# SCH_HackerCard_2024-08-29.net
KiCad netlist of a schematic drawn in EasyEDA
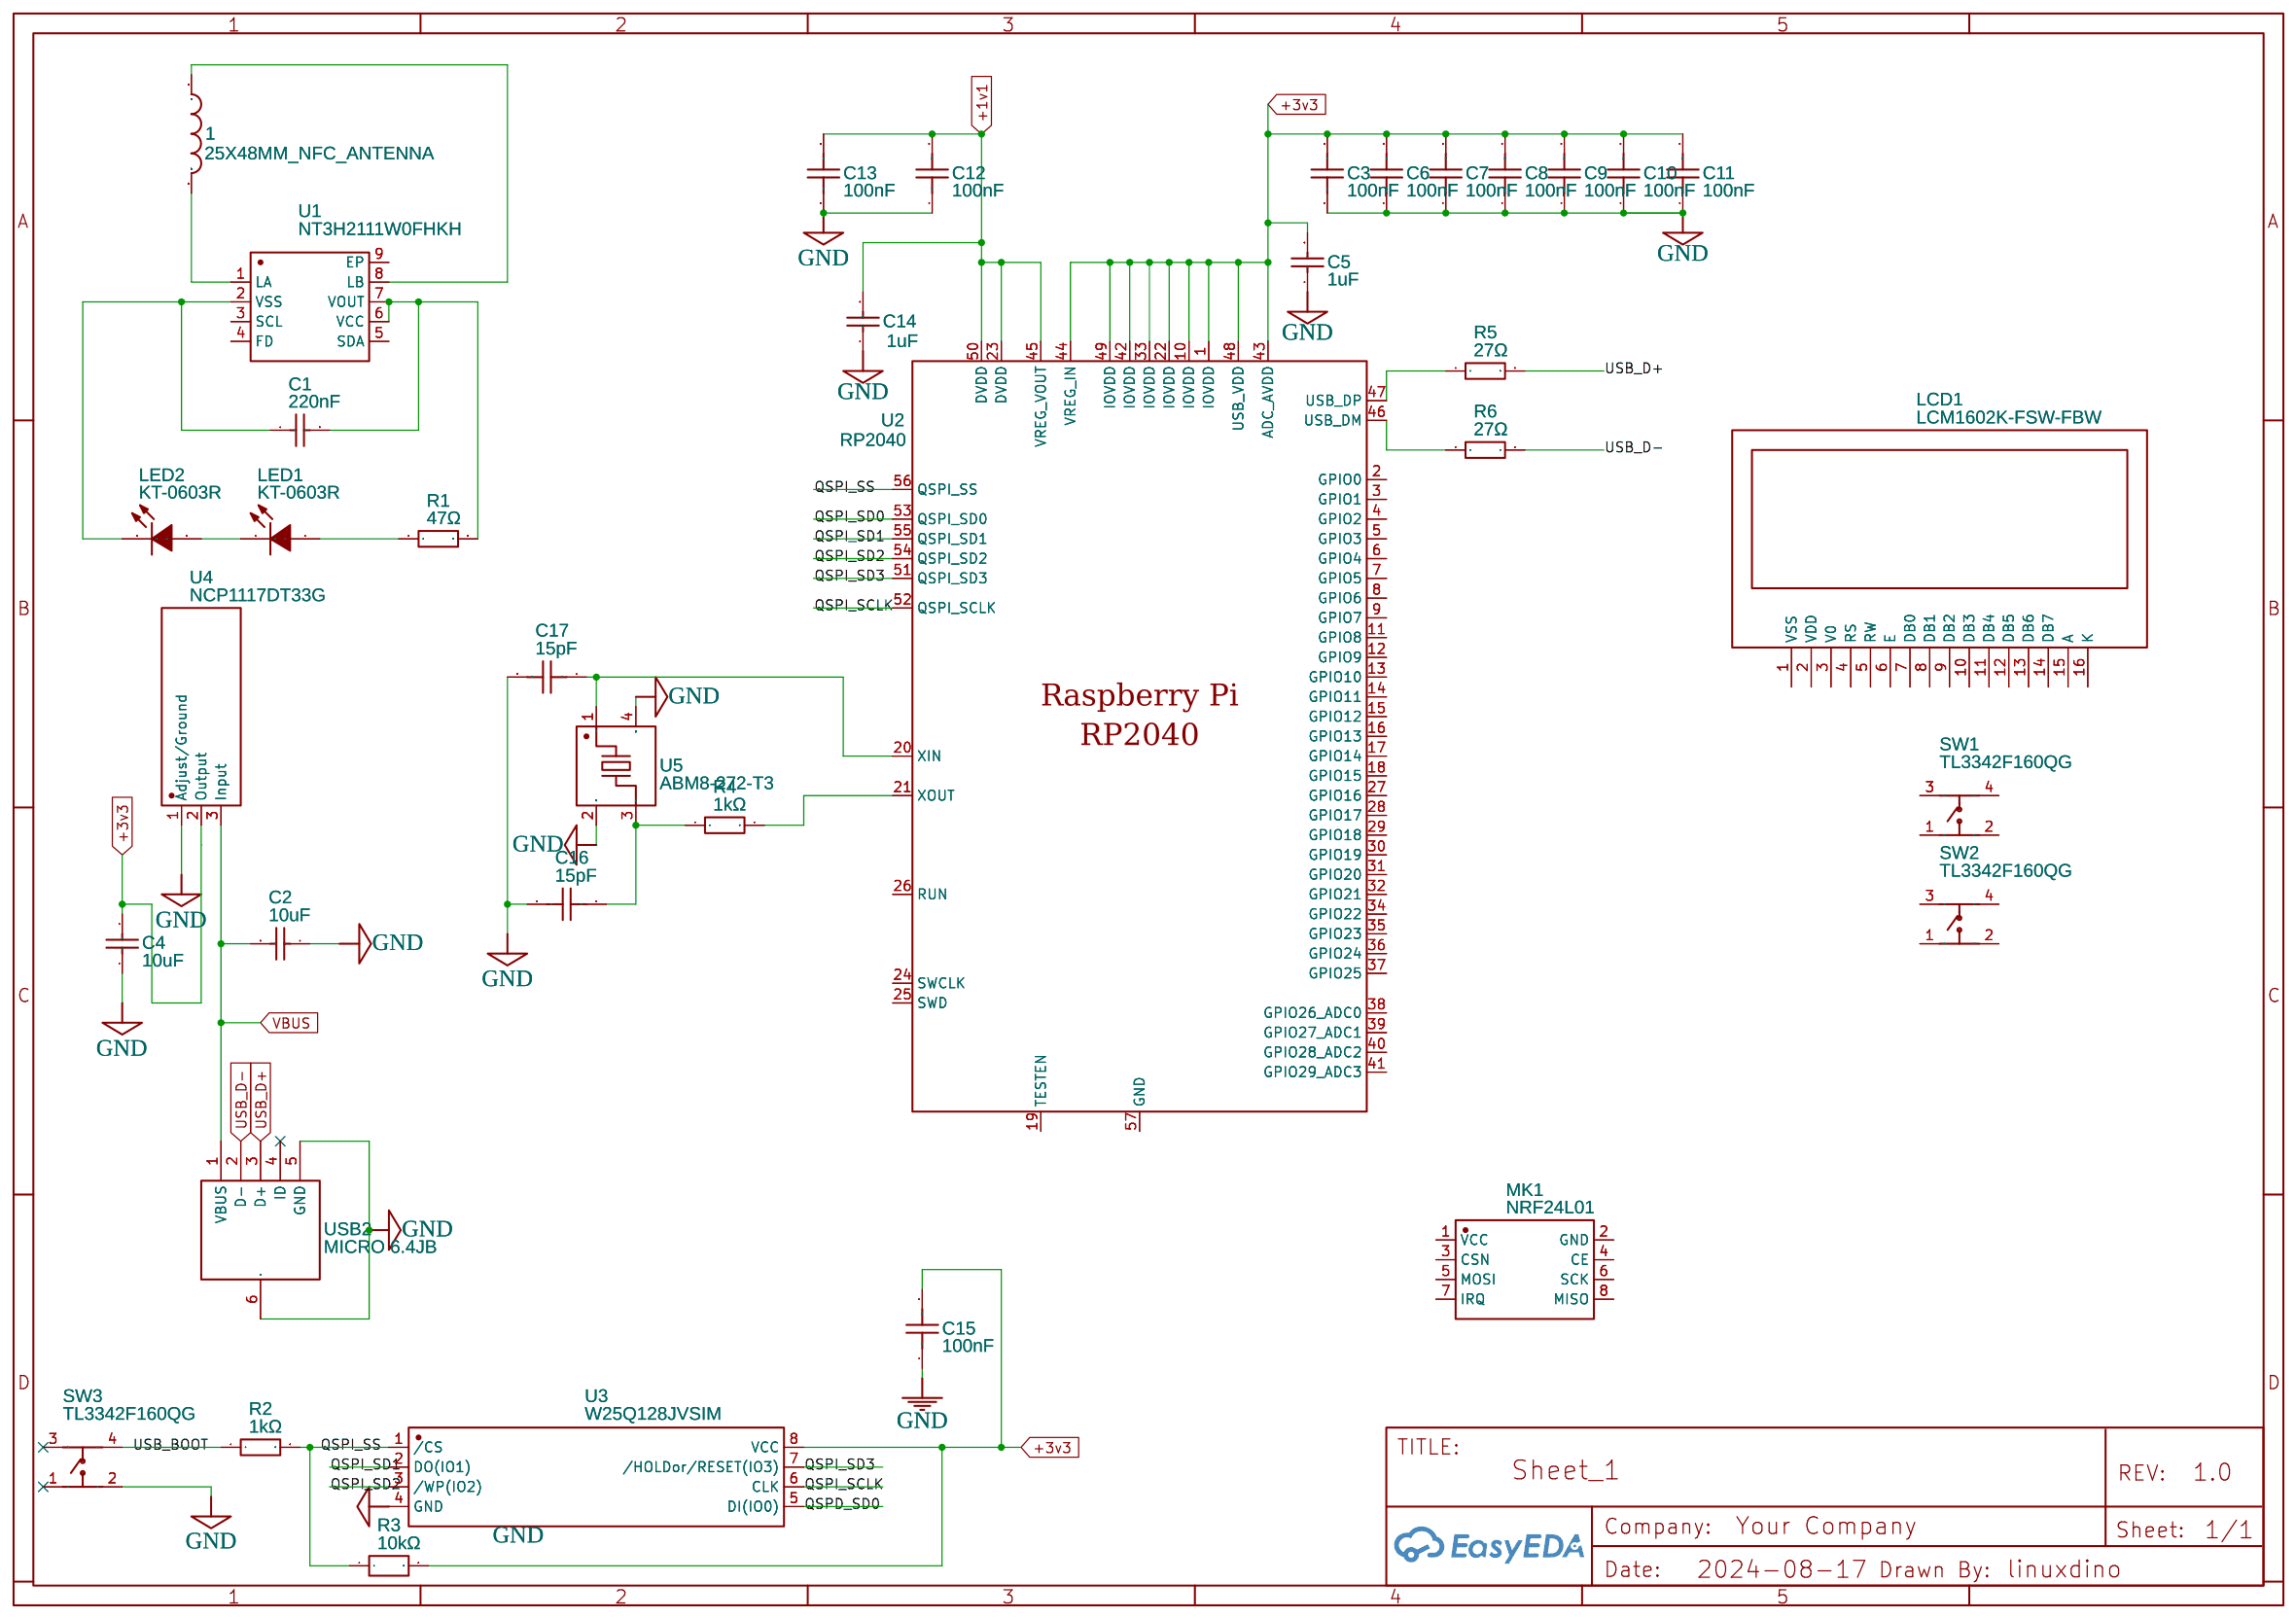
[diagram p0: schematic sheet]

(export (version "E")
  (design (tool "Eeschema 10.0.6"))
  (components
    (comp (ref "1") (value "25X48MM_NFC_ANTENNA") (libsource (lib "") (part "25X48MM_NFC_ANTENNA")))
    (comp (ref "C1")
      (value "220nF")
      (fields
        (field (name "Manufacturer Part") "CL10B224KA8NNNC")
        (field (name "Manufacturer") "SAMSUNG(三星)")
      )
      (libsource (lib "") (part "CL10B224KA8NNNC"))
    )
    (comp (ref "C2")
      (value "10uF")
      (fields
        (field (name "Manufacturer Part") "CL31A106KOHNNNE")
        (field (name "Manufacturer") "SAMSUNG(三星)")
      )
      (libsource (lib "") (part "CL31A106KOHNNNE_1"))
    )
    (comp (ref "C3")
      (value "100nF")
      (fields
        (field (name "Manufacturer Part") "CL10B104KB8NNNC")
        (field (name "Manufacturer") "SAMSUNG(三星)")
      )
      (libsource (lib "") (part "CL10B104KB8NNNC"))
    )
    (comp (ref "C4")
      (value "10uF")
      (fields
        (field (name "Manufacturer Part") "CL31A106KOHNNNE")
        (field (name "Manufacturer") "SAMSUNG(三星)")
      )
      (libsource (lib "") (part "CL31A106KOHNNNE"))
    )
    (comp (ref "C5")
      (value "1uF")
      (fields
        (field (name "Manufacturer Part") "CL10A105KO8NNNC")
        (field (name "Manufacturer") "SAMSUNG(三星)")
      )
      (libsource (lib "") (part "CL10A105KO8NNNC"))
    )
    (comp (ref "C6")
      (value "100nF")
      (fields
        (field (name "Manufacturer Part") "CL10B104KB8NNNC")
        (field (name "Manufacturer") "SAMSUNG(三星)")
      )
      (libsource (lib "") (part "CL10B104KB8NNNC"))
    )
    (comp (ref "C7")
      (value "100nF")
      (fields
        (field (name "Manufacturer Part") "CL10B104KB8NNNC")
        (field (name "Manufacturer") "SAMSUNG(三星)")
      )
      (libsource (lib "") (part "CL10B104KB8NNNC"))
    )
    (comp (ref "C8")
      (value "100nF")
      (fields
        (field (name "Manufacturer Part") "CL10B104KB8NNNC")
        (field (name "Manufacturer") "SAMSUNG(三星)")
      )
      (libsource (lib "") (part "CL10B104KB8NNNC"))
    )
    (comp (ref "C9")
      (value "100nF")
      (fields
        (field (name "Manufacturer Part") "CL10B104KB8NNNC")
        (field (name "Manufacturer") "SAMSUNG(三星)")
      )
      (libsource (lib "") (part "CL10B104KB8NNNC"))
    )
    (comp (ref "C10")
      (value "100nF")
      (fields
        (field (name "Manufacturer Part") "CL10B104KB8NNNC")
        (field (name "Manufacturer") "SAMSUNG(三星)")
      )
      (libsource (lib "") (part "CL10B104KB8NNNC"))
    )
    (comp (ref "C11")
      (value "100nF")
      (fields
        (field (name "Manufacturer Part") "CL10B104KB8NNNC")
        (field (name "Manufacturer") "SAMSUNG(三星)")
      )
      (libsource (lib "") (part "CL10B104KB8NNNC"))
    )
    (comp (ref "C12")
      (value "100nF")
      (fields
        (field (name "Manufacturer Part") "CL10B104KB8NNNC")
        (field (name "Manufacturer") "SAMSUNG(三星)")
      )
      (libsource (lib "") (part "CL10B104KB8NNNC"))
    )
    (comp (ref "C13")
      (value "100nF")
      (fields
        (field (name "Manufacturer Part") "CL10B104KB8NNNC")
        (field (name "Manufacturer") "SAMSUNG(三星)")
      )
      (libsource (lib "") (part "CL10B104KB8NNNC"))
    )
    (comp (ref "C14")
      (value "1uF")
      (fields
        (field (name "Manufacturer Part") "CL10A105KO8NNNC")
        (field (name "Manufacturer") "SAMSUNG(三星)")
      )
      (libsource (lib "") (part "CL10A105KO8NNNC"))
    )
    (comp (ref "C15")
      (value "100nF")
      (fields
        (field (name "Manufacturer Part") "CL10B104KB8NNNC")
        (field (name "Manufacturer") "SAMSUNG(三星)")
      )
      (libsource (lib "") (part "CL10B104KB8NNNC"))
    )
    (comp (ref "C16")
      (value "15pF")
      (fields (field (name "Manufacturer Part") "RF15N150J500CT") (field (name "Manufacturer") "Walsin(华新科)"))
      (libsource (lib "") (part "RF15N150J500CT"))
    )
    (comp (ref "C17")
      (value "15pF")
      (fields (field (name "Manufacturer Part") "RF15N150J500CT") (field (name "Manufacturer") "Walsin(华新科)"))
      (libsource (lib "") (part "RF15N150J500CT"))
    )
    (comp (ref "LCD1")
      (value "LCM1602K-FSW-FBW")
      (fields (field (name "Manufacturer") "LONTECH(厦门龙特)"))
      (libsource (lib "") (part "LCM1602K-FSW-FBW"))
    )
    (comp (ref "LED1")
      (value "KT-0603R")
      (fields (field (name "Manufacturer") "KENTO"))
      (libsource (lib "") (part "KT-0603R"))
    )
    (comp (ref "LED2")
      (value "KT-0603R")
      (fields (field (name "Manufacturer") "KENTO"))
      (libsource (lib "") (part "KT-0603R"))
    )
    (comp (ref "MK1")
      (value "NRF24L01")
      (fields (field (name "Manufacturer Part") "NF-04") (field (name "Manufacturer") "Ai-Thinker(安信可)"))
      (libsource (lib "") (part "NRF24L01"))
    )
    (comp (ref "R1")
      (value "47Ω")
      (fields
        (field (name "Manufacturer Part") "0603WAF470JT5E")
        (field (name "Manufacturer") "UNI-ROYAL(厚声)")
      )
      (libsource (lib "") (part "0603WAF470JT5E"))
    )
    (comp (ref "R2")
      (value "1kΩ")
      (fields
        (field (name "Manufacturer Part") "0603WAF1001T5E")
        (field (name "Manufacturer") "UNI-ROYAL(厚声)")
      )
      (libsource (lib "") (part "0603WAF1001T5E"))
    )
    (comp (ref "R3")
      (value "10kΩ")
      (fields (field (name "Manufacturer Part") "CR-03JL7---10K") (field (name "Manufacturer") "Viking(光颉)"))
      (libsource (lib "") (part "CR-03JL7---10K"))
    )
    (comp (ref "R4")
      (value "1kΩ")
      (fields
        (field (name "Manufacturer Part") "0603WAF1001T5E")
        (field (name "Manufacturer") "UNI-ROYAL(厚声)")
      )
      (libsource (lib "") (part "0603WAF1001T5E"))
    )
    (comp (ref "R5")
      (value "27Ω")
      (fields (field (name "Manufacturer Part") "RN732ATTD27R0B25") (field (name "Manufacturer") "KOA"))
      (libsource (lib "") (part "RN732ATTD27R0B25"))
    )
    (comp (ref "R6")
      (value "27Ω")
      (fields (field (name "Manufacturer Part") "RN732ATTD27R0B25") (field (name "Manufacturer") "KOA"))
      (libsource (lib "") (part "RN732ATTD27R0B25"))
    )
    (comp (ref "SW1")
      (value "TL3342F160QG")
      (fields (field (name "Manufacturer") "E-Switch"))
      (libsource (lib "") (part "TL3342F160QG"))
    )
    (comp (ref "SW2")
      (value "TL3342F160QG")
      (fields (field (name "Manufacturer") "E-Switch"))
      (libsource (lib "") (part "TL3342F160QG"))
    )
    (comp (ref "SW3")
      (value "TL3342F160QG")
      (fields (field (name "Manufacturer") "E-Switch"))
      (libsource (lib "") (part "TL3342F160QG"))
    )
    (comp (ref "U1")
      (value "NT3H2111W0FHKH")
      (fields (field (name "Manufacturer") "NXP(恩智浦)"))
      (libsource (lib "") (part "NT3H2111W0FHKH"))
    )
    (comp (ref "U2")
      (value "RP2040")
      (fields (field (name "Manufacturer") "Raspberry Pi(树莓派)"))
      (libsource (lib "") (part "RP2040"))
    )
    (comp (ref "U3")
      (value "W25Q128JVSIM")
      (fields (field (name "Manufacturer") "WINBOND(华邦)"))
      (libsource (lib "") (part "W25Q128JVSIM"))
    )
    (comp (ref "U4")
      (value "NCP1117DT33G")
      (fields (field (name "Manufacturer") "onsemi(安森美)"))
      (libsource (lib "") (part "NCP1117DT33G"))
    )
    (comp (ref "U5") (value "ABM8-272-T3") (libsource (lib "") (part "ABM8-272-T3")))
    (comp (ref "USB2")
      (value "MICRO 6.4JB")
      (fields (field (name "Manufacturer") "SHOU HAN(首韩)"))
      (libsource (lib "") (part "MICRO 6.4JB"))
    )
  )
  (nets
    (net (code "1") (name "+1v1") (class "Default")
      (node (ref "C12") (pin "2") (pinfunction "2_2") (pintype "unspecified"))
      (node (ref "C13") (pin "2") (pinfunction "2_2") (pintype "unspecified"))
      (node (ref "C14") (pin "2") (pinfunction "2_2") (pintype "input"))
      (node (ref "U2") (pin "23") (pinfunction "DVDD_23") (pintype "bidirectional"))
      (node (ref "U2") (pin "45") (pinfunction "VREG_VOUT_45") (pintype "bidirectional"))
      (node (ref "U2") (pin "50") (pinfunction "DVDD_50") (pintype "bidirectional"))
    )
    (net (code "2") (name "+3v3") (class "Default")
      (node (ref "C10") (pin "2") (pinfunction "2_2") (pintype "unspecified"))
      (node (ref "C11") (pin "2") (pinfunction "2_2") (pintype "unspecified"))
      (node (ref "C15") (pin "2") (pinfunction "2_2") (pintype "unspecified"))
      (node (ref "C3") (pin "2") (pinfunction "2_2") (pintype "unspecified"))
      (node (ref "C4") (pin "2") (pinfunction "2_2") (pintype "input"))
      (node (ref "C5") (pin "2") (pinfunction "2_2") (pintype "input"))
      (node (ref "C6") (pin "2") (pinfunction "2_2") (pintype "unspecified"))
      (node (ref "C7") (pin "2") (pinfunction "2_2") (pintype "unspecified"))
      (node (ref "C8") (pin "2") (pinfunction "2_2") (pintype "unspecified"))
      (node (ref "C9") (pin "2") (pinfunction "2_2") (pintype "unspecified"))
      (node (ref "R3") (pin "2") (pinfunction "2_2") (pintype "unspecified"))
      (node (ref "U2") (pin "1") (pinfunction "IOVDD_1") (pintype "bidirectional"))
      (node (ref "U2") (pin "10") (pinfunction "IOVDD_10") (pintype "bidirectional"))
      (node (ref "U2") (pin "22") (pinfunction "IOVDD_22") (pintype "bidirectional"))
      (node (ref "U2") (pin "33") (pinfunction "IOVDD_33") (pintype "bidirectional"))
      (node (ref "U2") (pin "42") (pinfunction "IOVDD_42") (pintype "bidirectional"))
      (node (ref "U2") (pin "43") (pinfunction "ADC_AVDD_43") (pintype "bidirectional"))
      (node (ref "U2") (pin "44") (pinfunction "VREG_IN_44") (pintype "bidirectional"))
      (node (ref "U2") (pin "48") (pinfunction "USB_VDD_48") (pintype "bidirectional"))
      (node (ref "U2") (pin "49") (pinfunction "IOVDD_49") (pintype "bidirectional"))
      (node (ref "U3") (pin "8") (pinfunction "VCC_8") (pintype "unspecified"))
      (node (ref "U4") (pin "2") (pinfunction "Output_2") (pintype "unspecified"))
    )
    (net (code "3") (name "/QSPD_SD0") (class "Default")
      (node (ref "U3") (pin "5") (pinfunction "DI(IO0)_5") (pintype "unspecified"))
    )
    (net (code "4") (name "/QSPI_SCLK") (class "Default")
      (node (ref "U2") (pin "52") (pinfunction "QSPI_SCLK_52") (pintype "output"))
      (node (ref "U3") (pin "6") (pinfunction "CLK_6") (pintype "unspecified"))
    )
    (net (code "5") (name "/QSPI_SD0") (class "Default")
      (node (ref "U2") (pin "53") (pinfunction "QSPI_SD0_53") (pintype "bidirectional"))
    )
    (net (code "6") (name "/QSPI_SD1") (class "Default")
      (node (ref "U2") (pin "55") (pinfunction "QSPI_SD1_55") (pintype "bidirectional"))
      (node (ref "U3") (pin "2") (pinfunction "DO(IO1)_2") (pintype "unspecified"))
    )
    (net (code "7") (name "/QSPI_SD2") (class "Default")
      (node (ref "U2") (pin "54") (pinfunction "QSPI_SD2_54") (pintype "bidirectional"))
      (node (ref "U3") (pin "3") (pinfunction "/WP(IO2)_3") (pintype "unspecified"))
    )
    (net (code "8") (name "/QSPI_SD3") (class "Default")
      (node (ref "U2") (pin "51") (pinfunction "QSPI_SD3_51") (pintype "bidirectional"))
      (node (ref "U3") (pin "7") (pinfunction "/HOLDor/RESET(IO3)_7") (pintype "unspecified"))
    )
    (net (code "9") (name "/QSPI_SS") (class "Default")
      (node (ref "R2") (pin "2") (pinfunction "2_2") (pintype "input"))
      (node (ref "R3") (pin "1") (pinfunction "1_1") (pintype "unspecified"))
      (node (ref "U2") (pin "56") (pinfunction "QSPI_SS_56") (pintype "bidirectional"))
      (node (ref "U3") (pin "1") (pinfunction "/CS_1") (pintype "unspecified"))
    )
    (net (code "10") (name "/USB_BOOT") (class "Default")
      (node (ref "R2") (pin "1") (pinfunction "1_1") (pintype "input"))
      (node (ref "SW3") (pin "4") (pinfunction "4_4") (pintype "unspecified"))
    )
    (net (code "11") (name "GND") (class "Default")
      (node (ref "C10") (pin "1") (pinfunction "1_1") (pintype "unspecified"))
      (node (ref "C11") (pin "1") (pinfunction "1_1") (pintype "unspecified"))
      (node (ref "C12") (pin "1") (pinfunction "1_1") (pintype "unspecified"))
      (node (ref "C13") (pin "1") (pinfunction "1_1") (pintype "unspecified"))
      (node (ref "C14") (pin "1") (pinfunction "1_1") (pintype "input"))
      (node (ref "C15") (pin "1") (pinfunction "1_1") (pintype "unspecified"))
      (node (ref "C16") (pin "2") (pinfunction "2_2") (pintype "unspecified"))
      (node (ref "C17") (pin "2") (pinfunction "2_2") (pintype "unspecified"))
      (node (ref "C2") (pin "1") (pinfunction "1_1") (pintype "input"))
      (node (ref "C3") (pin "1") (pinfunction "1_1") (pintype "unspecified"))
      (node (ref "C4") (pin "1") (pinfunction "1_1") (pintype "input"))
      (node (ref "C5") (pin "1") (pinfunction "1_1") (pintype "input"))
      (node (ref "C6") (pin "1") (pinfunction "1_1") (pintype "unspecified"))
      (node (ref "C7") (pin "1") (pinfunction "1_1") (pintype "unspecified"))
      (node (ref "C8") (pin "1") (pinfunction "1_1") (pintype "unspecified"))
      (node (ref "C9") (pin "1") (pinfunction "1_1") (pintype "unspecified"))
      (node (ref "SW3") (pin "2") (pinfunction "2_2") (pintype "unspecified"))
      (node (ref "U3") (pin "4") (pinfunction "GND_4") (pintype "unspecified"))
      (node (ref "U4") (pin "1") (pinfunction "Adjust/Ground_1") (pintype "unspecified"))
      (node (ref "U5") (pin "2") (pinfunction "GND_2") (pintype "input"))
      (node (ref "U5") (pin "4") (pinfunction "GND_4") (pintype "input"))
      (node (ref "USB2") (pin "5") (pinfunction "GND_5") (pintype "input"))
      (node (ref "USB2") (pin "6") (pinfunction "EH_6") (pintype "input"))
    )
    (net (code "12") (name "Net-(C16-Pad1)") (class "Default")
      (node (ref "C16") (pin "1") (pinfunction "1_1") (pintype "unspecified"))
      (node (ref "R4") (pin "1") (pinfunction "1_1") (pintype "input"))
      (node (ref "U5") (pin "3") (pinfunction "3_3") (pintype "input"))
    )
    (net (code "13") (name "Net-(LED1-A)") (class "Default")
      (node (ref "LED1") (pin "2") (pinfunction "A_2") (pintype "unspecified"))
      (node (ref "R1") (pin "1") (pinfunction "1_1") (pintype "input"))
    )
    (net (code "14") (name "Net-(LED1-K)") (class "Default")
      (node (ref "LED1") (pin "1") (pinfunction "K_1") (pintype "unspecified"))
      (node (ref "LED2") (pin "2") (pinfunction "A_2") (pintype "unspecified"))
    )
    (net (code "15") (name "Net-(LED2-K)") (class "Default")
      (node (ref "C1") (pin "1") (pinfunction "1_1") (pintype "input"))
      (node (ref "LED2") (pin "1") (pinfunction "K_1") (pintype "unspecified"))
      (node (ref "U1") (pin "2") (pinfunction "VSS_2") (pintype "unspecified"))
    )
    (net (code "16") (name "Net-(U1-LA)") (class "Default")
      (node (ref "1") (pin "P$2") (pinfunction "P$2_P$2") (pintype "bidirectional"))
      (node (ref "U1") (pin "1") (pinfunction "LA_1") (pintype "unspecified"))
    )
    (net (code "17") (name "Net-(U1-LB)") (class "Default")
      (node (ref "1") (pin "P$1") (pinfunction "P$1_P$1") (pintype "bidirectional"))
      (node (ref "U1") (pin "8") (pinfunction "LB_8") (pintype "unspecified"))
    )
    (net (code "18") (name "Net-(U1-VCC)") (class "Default")
      (node (ref "C1") (pin "2") (pinfunction "2_2") (pintype "input"))
      (node (ref "R1") (pin "2") (pinfunction "2_2") (pintype "input"))
      (node (ref "U1") (pin "6") (pinfunction "VCC_6") (pintype "unspecified"))
      (node (ref "U1") (pin "7") (pinfunction "VOUT_7") (pintype "unspecified"))
    )
    (net (code "19") (name "Net-(U2-USB_DM)") (class "Default")
      (node (ref "R6") (pin "1") (pinfunction "1_1") (pintype "unspecified"))
      (node (ref "U2") (pin "46") (pinfunction "USB_DM_46") (pintype "bidirectional"))
    )
    (net (code "20") (name "Net-(U2-USB_DP)") (class "Default")
      (node (ref "R5") (pin "1") (pinfunction "1_1") (pintype "unspecified"))
      (node (ref "U2") (pin "47") (pinfunction "USB_DP_47") (pintype "bidirectional"))
    )
    (net (code "21") (name "Net-(U2-XIN)") (class "Default")
      (node (ref "C17") (pin "1") (pinfunction "1_1") (pintype "unspecified"))
      (node (ref "U2") (pin "20") (pinfunction "XIN_20") (pintype "input"))
      (node (ref "U5") (pin "1") (pinfunction "1_1") (pintype "input"))
    )
    (net (code "22") (name "Net-(U2-XOUT)") (class "Default")
      (node (ref "R4") (pin "2") (pinfunction "2_2") (pintype "input"))
      (node (ref "U2") (pin "21") (pinfunction "XOUT_21") (pintype "unspecified"))
    )
    (net (code "23") (name "USB_D+") (class "Default")
      (node (ref "R5") (pin "2") (pinfunction "2_2") (pintype "unspecified"))
      (node (ref "USB2") (pin "3") (pinfunction "D+_3") (pintype "input"))
    )
    (net (code "24") (name "USB_D-") (class "Default")
      (node (ref "R6") (pin "2") (pinfunction "2_2") (pintype "unspecified"))
      (node (ref "USB2") (pin "2") (pinfunction "D-_2") (pintype "input"))
    )
    (net (code "25") (name "VBUS") (class "Default")
      (node (ref "C2") (pin "2") (pinfunction "2_2") (pintype "input"))
      (node (ref "U4") (pin "3") (pinfunction "Input_3") (pintype "unspecified"))
      (node (ref "USB2") (pin "1") (pinfunction "VBUS_1") (pintype "input"))
    )
    (net (code "26") (name "unconnected-(LCD1-A-Pad15)") (class "Default")
      (node (ref "LCD1") (pin "15") (pinfunction "A_15") (pintype "unspecified"))
    )
    (net (code "27") (name "unconnected-(LCD1-DB0-Pad7)") (class "Default")
      (node (ref "LCD1") (pin "7") (pinfunction "DB0_7") (pintype "unspecified"))
    )
    (net (code "28") (name "unconnected-(LCD1-DB1-Pad8)") (class "Default")
      (node (ref "LCD1") (pin "8") (pinfunction "DB1_8") (pintype "unspecified"))
    )
    (net (code "29") (name "unconnected-(LCD1-DB2-Pad9)") (class "Default")
      (node (ref "LCD1") (pin "9") (pinfunction "DB2_9") (pintype "unspecified"))
    )
    (net (code "30") (name "unconnected-(LCD1-DB3-Pad10)") (class "Default")
      (node (ref "LCD1") (pin "10") (pinfunction "DB3_10") (pintype "unspecified"))
    )
    (net (code "31") (name "unconnected-(LCD1-DB4-Pad11)") (class "Default")
      (node (ref "LCD1") (pin "11") (pinfunction "DB4_11") (pintype "unspecified"))
    )
    (net (code "32") (name "unconnected-(LCD1-DB5-Pad12)") (class "Default")
      (node (ref "LCD1") (pin "12") (pinfunction "DB5_12") (pintype "unspecified"))
    )
    (net (code "33") (name "unconnected-(LCD1-DB6-Pad13)") (class "Default")
      (node (ref "LCD1") (pin "13") (pinfunction "DB6_13") (pintype "unspecified"))
    )
    (net (code "34") (name "unconnected-(LCD1-DB7-Pad14)") (class "Default")
      (node (ref "LCD1") (pin "14") (pinfunction "DB7_14") (pintype "unspecified"))
    )
    (net (code "35") (name "unconnected-(LCD1-E-Pad6)") (class "Default")
      (node (ref "LCD1") (pin "6") (pinfunction "E_6") (pintype "unspecified"))
    )
    (net (code "36") (name "unconnected-(LCD1-K-Pad16)") (class "Default")
      (node (ref "LCD1") (pin "16") (pinfunction "K_16") (pintype "unspecified"))
    )
    (net (code "37") (name "unconnected-(LCD1-RS-Pad4)") (class "Default")
      (node (ref "LCD1") (pin "4") (pinfunction "RS_4") (pintype "unspecified"))
    )
    (net (code "38") (name "unconnected-(LCD1-RW-Pad5)") (class "Default")
      (node (ref "LCD1") (pin "5") (pinfunction "RW_5") (pintype "unspecified"))
    )
    (net (code "39") (name "unconnected-(LCD1-V0-Pad3)") (class "Default")
      (node (ref "LCD1") (pin "3") (pinfunction "V0_3") (pintype "unspecified"))
    )
    (net (code "40") (name "unconnected-(LCD1-VDD-Pad2)") (class "Default")
      (node (ref "LCD1") (pin "2") (pinfunction "VDD_2") (pintype "unspecified"))
    )
    (net (code "41") (name "unconnected-(LCD1-VSS-Pad1)") (class "Default")
      (node (ref "LCD1") (pin "1") (pinfunction "VSS_1") (pintype "unspecified"))
    )
    (net (code "42") (name "unconnected-(MK1-CE-Pad4)") (class "Default")
      (node (ref "MK1") (pin "4") (pinfunction "CE_4") (pintype "unspecified"))
    )
    (net (code "43") (name "unconnected-(MK1-CSN-Pad3)") (class "Default")
      (node (ref "MK1") (pin "3") (pinfunction "CSN_3") (pintype "unspecified"))
    )
    (net (code "44") (name "unconnected-(MK1-GND-Pad2)") (class "Default")
      (node (ref "MK1") (pin "2") (pinfunction "GND_2") (pintype "unspecified"))
    )
    (net (code "45") (name "unconnected-(MK1-IRQ-Pad7)") (class "Default")
      (node (ref "MK1") (pin "7") (pinfunction "IRQ_7") (pintype "unspecified"))
    )
    (net (code "46") (name "unconnected-(MK1-MISO-Pad8)") (class "Default")
      (node (ref "MK1") (pin "8") (pinfunction "MISO_8") (pintype "unspecified"))
    )
    (net (code "47") (name "unconnected-(MK1-MOSI-Pad5)") (class "Default")
      (node (ref "MK1") (pin "5") (pinfunction "MOSI_5") (pintype "unspecified"))
    )
    (net (code "48") (name "unconnected-(MK1-SCK-Pad6)") (class "Default")
      (node (ref "MK1") (pin "6") (pinfunction "SCK_6") (pintype "unspecified"))
    )
    (net (code "49") (name "unconnected-(MK1-VCC-Pad1)") (class "Default")
      (node (ref "MK1") (pin "1") (pinfunction "VCC_1") (pintype "unspecified"))
    )
    (net (code "50") (name "unconnected-(SW1-Pad1)") (class "Default")
      (node (ref "SW1") (pin "1") (pinfunction "1_1") (pintype "unspecified"))
    )
    (net (code "51") (name "unconnected-(SW1-Pad2)") (class "Default")
      (node (ref "SW1") (pin "2") (pinfunction "2_2") (pintype "unspecified"))
    )
    (net (code "52") (name "unconnected-(SW1-Pad3)") (class "Default")
      (node (ref "SW1") (pin "3") (pinfunction "3_3") (pintype "unspecified"))
    )
    (net (code "53") (name "unconnected-(SW1-Pad4)") (class "Default")
      (node (ref "SW1") (pin "4") (pinfunction "4_4") (pintype "unspecified"))
    )
    (net (code "54") (name "unconnected-(SW2-Pad1)") (class "Default")
      (node (ref "SW2") (pin "1") (pinfunction "1_1") (pintype "unspecified"))
    )
    (net (code "55") (name "unconnected-(SW2-Pad2)") (class "Default")
      (node (ref "SW2") (pin "2") (pinfunction "2_2") (pintype "unspecified"))
    )
    (net (code "56") (name "unconnected-(SW2-Pad3)") (class "Default")
      (node (ref "SW2") (pin "3") (pinfunction "3_3") (pintype "unspecified"))
    )
    (net (code "57") (name "unconnected-(SW2-Pad4)") (class "Default")
      (node (ref "SW2") (pin "4") (pinfunction "4_4") (pintype "unspecified"))
    )
    (net (code "58") (name "unconnected-(SW3-Pad1)") (class "Default")
      (node (ref "SW3") (pin "1") (pinfunction "1_1") (pintype "unspecified+no_connect"))
    )
    (net (code "59") (name "unconnected-(SW3-Pad3)") (class "Default")
      (node (ref "SW3") (pin "3") (pinfunction "3_3") (pintype "unspecified+no_connect"))
    )
    (net (code "60") (name "unconnected-(U1-EP-Pad9)") (class "Default")
      (node (ref "U1") (pin "9") (pinfunction "EP_9") (pintype "unspecified"))
    )
    (net (code "61") (name "unconnected-(U1-FD-Pad4)") (class "Default")
      (node (ref "U1") (pin "4") (pinfunction "FD_4") (pintype "unspecified"))
    )
    (net (code "62") (name "unconnected-(U1-SCL-Pad3)") (class "Default")
      (node (ref "U1") (pin "3") (pinfunction "SCL_3") (pintype "unspecified"))
    )
    (net (code "63") (name "unconnected-(U1-SDA-Pad5)") (class "Default")
      (node (ref "U1") (pin "5") (pinfunction "SDA_5") (pintype "unspecified"))
    )
    (net (code "64") (name "unconnected-(U2-GND-Pad57)") (class "Default")
      (node (ref "U2") (pin "57") (pinfunction "GND_57") (pintype "bidirectional"))
    )
    (net (code "65") (name "unconnected-(U2-GPIO0-Pad2)") (class "Default")
      (node (ref "U2") (pin "2") (pinfunction "GPIO0_2") (pintype "bidirectional"))
    )
    (net (code "66") (name "unconnected-(U2-GPIO1-Pad3)") (class "Default")
      (node (ref "U2") (pin "3") (pinfunction "GPIO1_3") (pintype "bidirectional"))
    )
    (net (code "67") (name "unconnected-(U2-GPIO2-Pad4)") (class "Default")
      (node (ref "U2") (pin "4") (pinfunction "GPIO2_4") (pintype "bidirectional"))
    )
    (net (code "68") (name "unconnected-(U2-GPIO3-Pad5)") (class "Default")
      (node (ref "U2") (pin "5") (pinfunction "GPIO3_5") (pintype "bidirectional"))
    )
    (net (code "69") (name "unconnected-(U2-GPIO4-Pad6)") (class "Default")
      (node (ref "U2") (pin "6") (pinfunction "GPIO4_6") (pintype "bidirectional"))
    )
    (net (code "70") (name "unconnected-(U2-GPIO5-Pad7)") (class "Default")
      (node (ref "U2") (pin "7") (pinfunction "GPIO5_7") (pintype "bidirectional"))
    )
    (net (code "71") (name "unconnected-(U2-GPIO6-Pad8)") (class "Default")
      (node (ref "U2") (pin "8") (pinfunction "GPIO6_8") (pintype "bidirectional"))
    )
    (net (code "72") (name "unconnected-(U2-GPIO7-Pad9)") (class "Default")
      (node (ref "U2") (pin "9") (pinfunction "GPIO7_9") (pintype "bidirectional"))
    )
    (net (code "73") (name "unconnected-(U2-GPIO8-Pad11)") (class "Default")
      (node (ref "U2") (pin "11") (pinfunction "GPIO8_11") (pintype "bidirectional"))
    )
    (net (code "74") (name "unconnected-(U2-GPIO9-Pad12)") (class "Default")
      (node (ref "U2") (pin "12") (pinfunction "GPIO9_12") (pintype "bidirectional"))
    )
    (net (code "75") (name "unconnected-(U2-GPIO10-Pad13)") (class "Default")
      (node (ref "U2") (pin "13") (pinfunction "GPIO10_13") (pintype "bidirectional"))
    )
    (net (code "76") (name "unconnected-(U2-GPIO11-Pad14)") (class "Default")
      (node (ref "U2") (pin "14") (pinfunction "GPIO11_14") (pintype "bidirectional"))
    )
    (net (code "77") (name "unconnected-(U2-GPIO12-Pad15)") (class "Default")
      (node (ref "U2") (pin "15") (pinfunction "GPIO12_15") (pintype "bidirectional"))
    )
    (net (code "78") (name "unconnected-(U2-GPIO13-Pad16)") (class "Default")
      (node (ref "U2") (pin "16") (pinfunction "GPIO13_16") (pintype "bidirectional"))
    )
    (net (code "79") (name "unconnected-(U2-GPIO14-Pad17)") (class "Default")
      (node (ref "U2") (pin "17") (pinfunction "GPIO14_17") (pintype "bidirectional"))
    )
    (net (code "80") (name "unconnected-(U2-GPIO15-Pad18)") (class "Default")
      (node (ref "U2") (pin "18") (pinfunction "GPIO15_18") (pintype "bidirectional"))
    )
    (net (code "81") (name "unconnected-(U2-GPIO16-Pad27)") (class "Default")
      (node (ref "U2") (pin "27") (pinfunction "GPIO16_27") (pintype "bidirectional"))
    )
    (net (code "82") (name "unconnected-(U2-GPIO17-Pad28)") (class "Default")
      (node (ref "U2") (pin "28") (pinfunction "GPIO17_28") (pintype "bidirectional"))
    )
    (net (code "83") (name "unconnected-(U2-GPIO18-Pad29)") (class "Default")
      (node (ref "U2") (pin "29") (pinfunction "GPIO18_29") (pintype "bidirectional"))
    )
    (net (code "84") (name "unconnected-(U2-GPIO19-Pad30)") (class "Default")
      (node (ref "U2") (pin "30") (pinfunction "GPIO19_30") (pintype "bidirectional"))
    )
    (net (code "85") (name "unconnected-(U2-GPIO20-Pad31)") (class "Default")
      (node (ref "U2") (pin "31") (pinfunction "GPIO20_31") (pintype "bidirectional"))
    )
    (net (code "86") (name "unconnected-(U2-GPIO21-Pad32)") (class "Default")
      (node (ref "U2") (pin "32") (pinfunction "GPIO21_32") (pintype "bidirectional"))
    )
    (net (code "87") (name "unconnected-(U2-GPIO22-Pad34)") (class "Default")
      (node (ref "U2") (pin "34") (pinfunction "GPIO22_34") (pintype "bidirectional"))
    )
    (net (code "88") (name "unconnected-(U2-GPIO23-Pad35)") (class "Default")
      (node (ref "U2") (pin "35") (pinfunction "GPIO23_35") (pintype "bidirectional"))
    )
    (net (code "89") (name "unconnected-(U2-GPIO24-Pad36)") (class "Default")
      (node (ref "U2") (pin "36") (pinfunction "GPIO24_36") (pintype "bidirectional"))
    )
    (net (code "90") (name "unconnected-(U2-GPIO25-Pad37)") (class "Default")
      (node (ref "U2") (pin "37") (pinfunction "GPIO25_37") (pintype "bidirectional"))
    )
    (net (code "91") (name "unconnected-(U2-GPIO26_ADC0-Pad38)") (class "Default")
      (node (ref "U2") (pin "38") (pinfunction "GPIO26_ADC0_38") (pintype "bidirectional"))
    )
    (net (code "92") (name "unconnected-(U2-GPIO27_ADC1-Pad39)") (class "Default")
      (node (ref "U2") (pin "39") (pinfunction "GPIO27_ADC1_39") (pintype "bidirectional"))
    )
    (net (code "93") (name "unconnected-(U2-GPIO28_ADC2-Pad40)") (class "Default")
      (node (ref "U2") (pin "40") (pinfunction "GPIO28_ADC2_40") (pintype "bidirectional"))
    )
    (net (code "94") (name "unconnected-(U2-GPIO29_ADC3-Pad41)") (class "Default")
      (node (ref "U2") (pin "41") (pinfunction "GPIO29_ADC3_41") (pintype "bidirectional"))
    )
    (net (code "95") (name "unconnected-(U2-RUN-Pad26)") (class "Default")
      (node (ref "U2") (pin "26") (pinfunction "RUN_26") (pintype "input"))
    )
    (net (code "96") (name "unconnected-(U2-SWCLK-Pad24)") (class "Default")
      (node (ref "U2") (pin "24") (pinfunction "SWCLK_24") (pintype "output"))
    )
    (net (code "97") (name "unconnected-(U2-SWD-Pad25)") (class "Default")
      (node (ref "U2") (pin "25") (pinfunction "SWD_25") (pintype "bidirectional"))
    )
    (net (code "98") (name "unconnected-(U2-TESTEN-Pad19)") (class "Default")
      (node (ref "U2") (pin "19") (pinfunction "TESTEN_19") (pintype "unspecified"))
    )
    (net (code "99") (name "unconnected-(USB2-ID-Pad4)") (class "Default")
      (node (ref "USB2") (pin "4") (pinfunction "ID_4") (pintype "input+no_connect"))
    )
  )
)
